# sensor_card.net
KiCad netlist of a schematic drawn in EAGLE
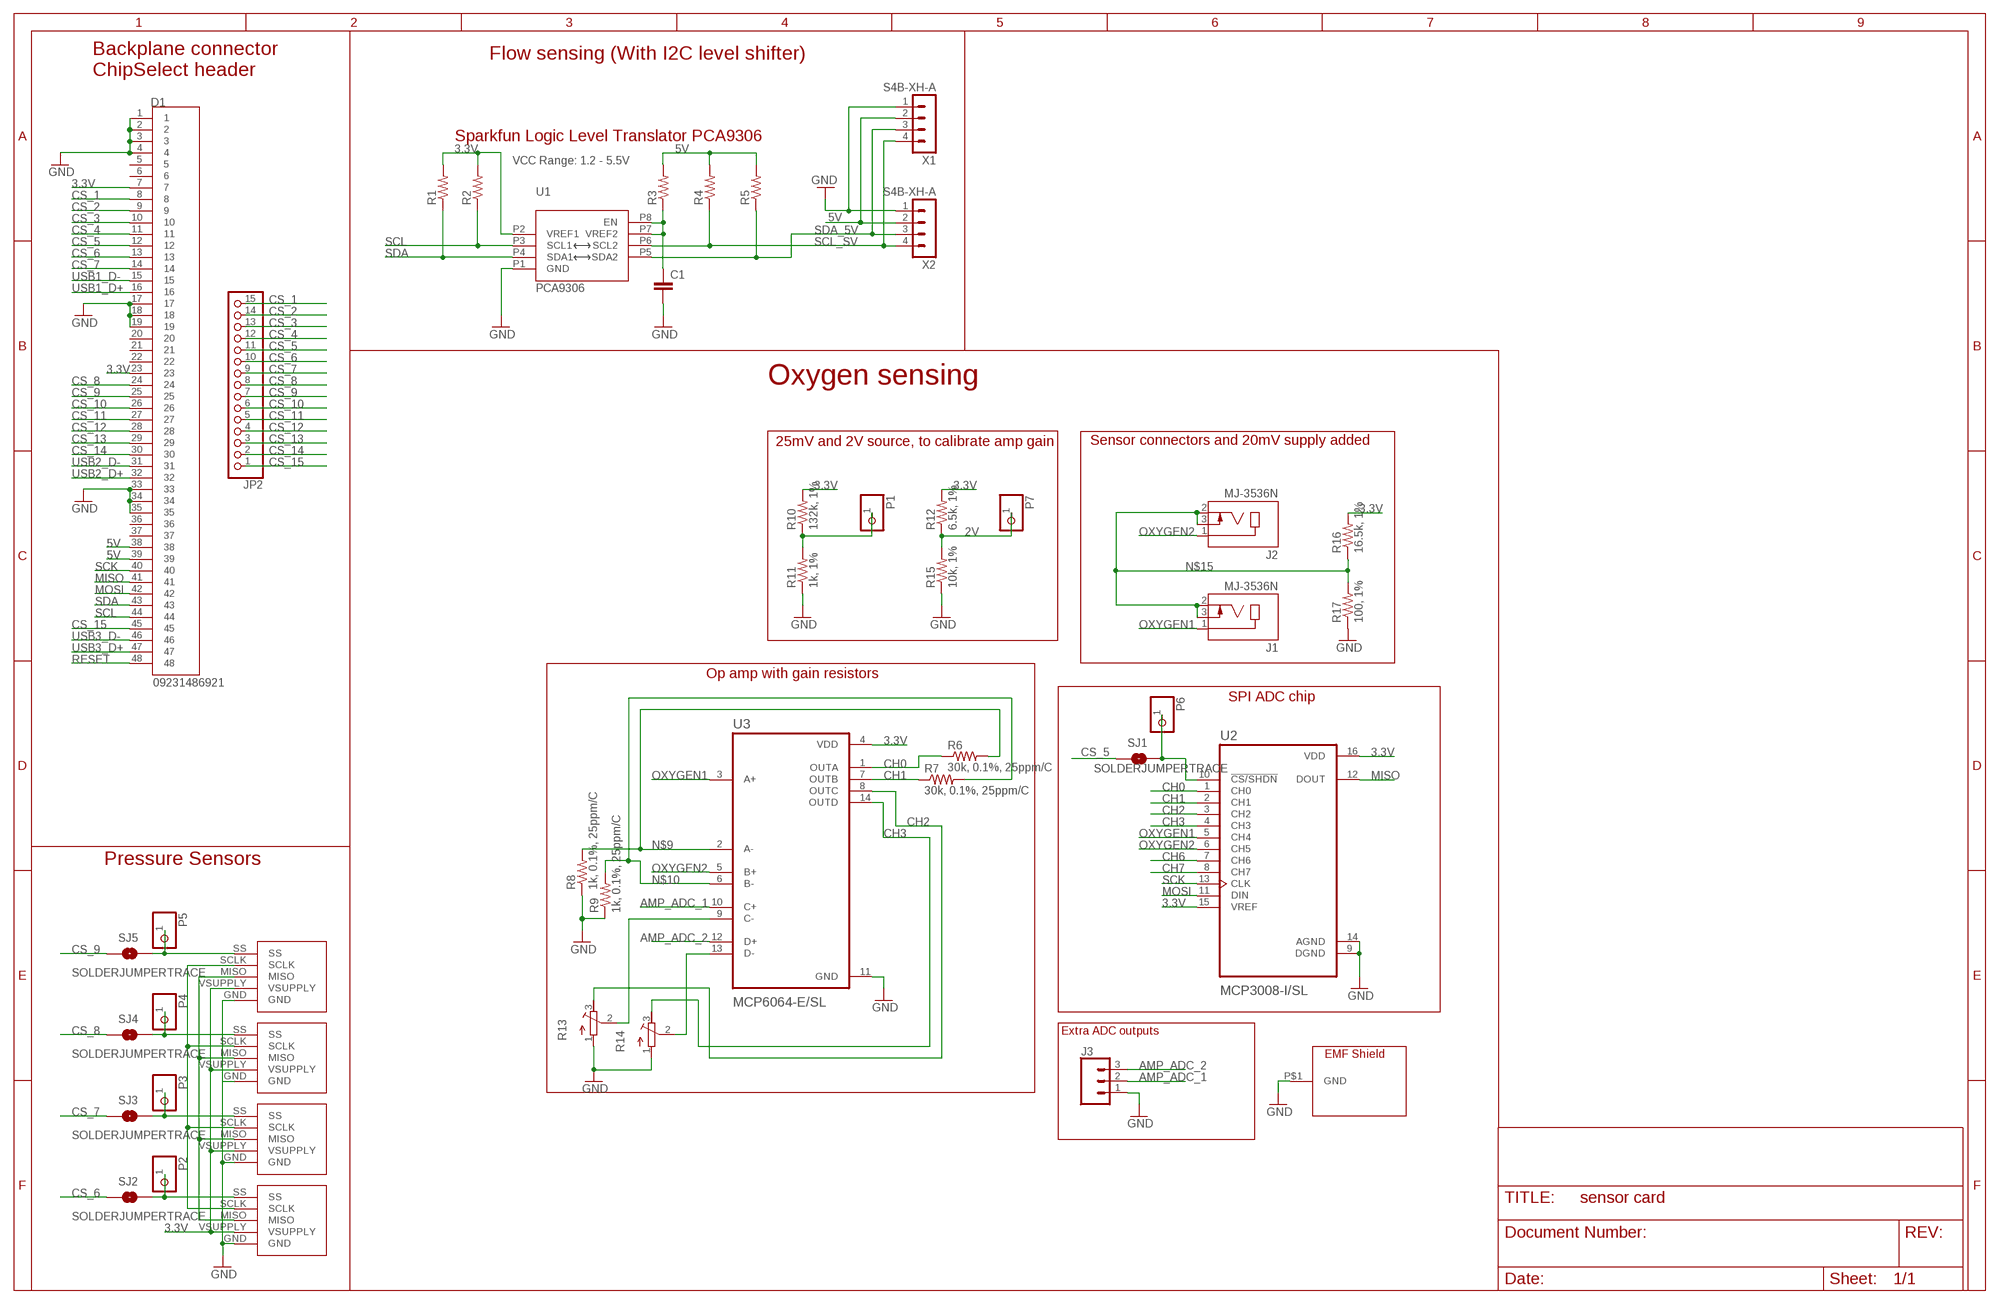
[diagram p0: schematic, sheet 1]

(export (version "E")
  (design (tool "Eeschema 10.0.6"))
  (components
    (comp (ref "C1")
      (value "100pF")
      (footprint "eagle-import:0805")
      (libsource (lib "eagle-import") (part "CAP0805"))
    )
    (comp (ref "D1")
      (value "09231486921")
      (footprint "eagle-import:HARTING_09231486921")
      (libsource (lib "eagle-import") (part "09231486921"))
    )
    (comp (ref "J1")
      (value "MJ-3536N")
      (footprint "eagle-import:CUI_MJ-3536N")
      (libsource (lib "eagle-import") (part "MJ-3536N"))
    )
    (comp (ref "J2")
      (value "MJ-3536N")
      (footprint "eagle-import:CUI_MJ-3536N")
      (libsource (lib "eagle-import") (part "MJ-3536N"))
    )
    (comp (ref "J3")
      (value "CONN_03")
      (footprint "eagle-import:1X03")
      (libsource (lib "eagle-import") (part "CONN_03"))
    )
    (comp (ref "JP2")
      (value "PINHD-1X15")
      (footprint "eagle-import:1X15")
      (libsource (lib "eagle-import") (part "PINHD-1X15"))
    )
    (comp (ref "P1")
      (value "PINHD-1X1")
      (footprint "eagle-import:1X01")
      (libsource (lib "eagle-import") (part "PINHD-1X1"))
    )
    (comp (ref "P2")
      (value "PINHD-1X1")
      (footprint "eagle-import:1X01")
      (libsource (lib "eagle-import") (part "PINHD-1X1"))
    )
    (comp (ref "P3")
      (value "PINHD-1X1")
      (footprint "eagle-import:1X01")
      (libsource (lib "eagle-import") (part "PINHD-1X1"))
    )
    (comp (ref "P4")
      (value "PINHD-1X1")
      (footprint "eagle-import:1X01")
      (libsource (lib "eagle-import") (part "PINHD-1X1"))
    )
    (comp (ref "P5")
      (value "PINHD-1X1")
      (footprint "eagle-import:1X01")
      (libsource (lib "eagle-import") (part "PINHD-1X1"))
    )
    (comp (ref "P6")
      (value "PINHD-1X1")
      (footprint "eagle-import:1X01")
      (libsource (lib "eagle-import") (part "PINHD-1X1"))
    )
    (comp (ref "P7")
      (value "PINHD-1X1")
      (footprint "eagle-import:1X01")
      (libsource (lib "eagle-import") (part "PINHD-1X1"))
    )
    (comp (ref "R1")
      (value "2.2k")
      (footprint "eagle-import:0805")
      (libsource (lib "eagle-import") (part "RESISTOR0805-RES"))
    )
    (comp (ref "R2")
      (value "2.2k")
      (footprint "eagle-import:0805")
      (libsource (lib "eagle-import") (part "RESISTOR0805-RES"))
    )
    (comp (ref "R3")
      (value "200K")
      (footprint "eagle-import:0805")
      (libsource (lib "eagle-import") (part "RESISTOR0805-RES"))
    )
    (comp (ref "R4")
      (value "2.2k")
      (footprint "eagle-import:0805")
      (libsource (lib "eagle-import") (part "RESISTOR0805-RES"))
    )
    (comp (ref "R5")
      (value "2.2k")
      (footprint "eagle-import:0805")
      (libsource (lib "eagle-import") (part "RESISTOR0805-RES"))
    )
    (comp (ref "R6")
      (value "30k, 0.1%, 25ppm/C")
      (footprint "eagle-import:0805")
      (libsource (lib "eagle-import") (part "RESISTOR0805-RES"))
    )
    (comp (ref "R7")
      (value "30k, 0.1%, 25ppm/C")
      (footprint "eagle-import:0805")
      (libsource (lib "eagle-import") (part "RESISTOR0805-RES"))
    )
    (comp (ref "R8")
      (value "1k, 0.1%, 25ppm/C")
      (footprint "eagle-import:0805")
      (libsource (lib "eagle-import") (part "RESISTOR0805-RES"))
    )
    (comp (ref "R9")
      (value "1k, 0.1%, 25ppm/C")
      (footprint "eagle-import:0805")
      (libsource (lib "eagle-import") (part "RESISTOR0805-RES"))
    )
    (comp (ref "R10")
      (value "132k, 1%")
      (footprint "eagle-import:0805")
      (libsource (lib "eagle-import") (part "RESISTOR0805-RES"))
    )
    (comp (ref "R11")
      (value "1k, 1%")
      (footprint "eagle-import:0805")
      (libsource (lib "eagle-import") (part "RESISTOR0805-RES"))
    )
    (comp (ref "R12")
      (value "6.5k, 1%")
      (footprint "eagle-import:0805")
      (libsource (lib "eagle-import") (part "RESISTOR0805-RES"))
    )
    (comp (ref "R13")
      (value "R-TRIMM3214W")
      (footprint "eagle-import:RTRIM3214W")
      (libsource (lib "eagle-import") (part "R-TRIMM3214W"))
    )
    (comp (ref "R14")
      (value "R-TRIMM3214W")
      (footprint "eagle-import:RTRIM3214W")
      (libsource (lib "eagle-import") (part "R-TRIMM3214W"))
    )
    (comp (ref "R15")
      (value "10k, 1%")
      (footprint "eagle-import:0805")
      (libsource (lib "eagle-import") (part "RESISTOR0805-RES"))
    )
    (comp (ref "R16")
      (value "16.5k, 1%")
      (footprint "eagle-import:0805")
      (libsource (lib "eagle-import") (part "RESISTOR0805-RES"))
    )
    (comp (ref "R17")
      (value "100, 1%")
      (footprint "eagle-import:0805")
      (libsource (lib "eagle-import") (part "RESISTOR0805-RES"))
    )
    (comp (ref "SJ1")
      (value "SOLDERJUMPERTRACE")
      (footprint "eagle-import:SJ_2S-TRACE")
      (libsource (lib "eagle-import") (part "SOLDERJUMPERTRACE"))
    )
    (comp (ref "SJ2")
      (value "SOLDERJUMPERTRACE")
      (footprint "eagle-import:SJ_2S-TRACE")
      (libsource (lib "eagle-import") (part "SOLDERJUMPERTRACE"))
    )
    (comp (ref "SJ3")
      (value "SOLDERJUMPERTRACE")
      (footprint "eagle-import:SJ_2S-TRACE")
      (libsource (lib "eagle-import") (part "SOLDERJUMPERTRACE"))
    )
    (comp (ref "SJ4")
      (value "SOLDERJUMPERTRACE")
      (footprint "eagle-import:SJ_2S-TRACE")
      (libsource (lib "eagle-import") (part "SOLDERJUMPERTRACE"))
    )
    (comp (ref "SJ5")
      (value "SOLDERJUMPERTRACE")
      (footprint "eagle-import:SJ_2S-TRACE")
      (libsource (lib "eagle-import") (part "SOLDERJUMPERTRACE"))
    )
    (comp (ref "U$1")
      (value "SCCDRRV100MDSA3SSCDRRV100MDSA3")
      (footprint "eagle-import:DIP1270W53P254L1303H508Q8B")
      (libsource (lib "eagle-import") (part "SCCDRRV100MDSA3SSCDRRV100MDSA3"))
    )
    (comp (ref "U$2")
      (value "EMI_SHIELD")
      (footprint "eagle-import:3671250")
      (libsource (lib "eagle-import") (part "EMI_SHIELD"))
    )
    (comp (ref "U$3")
      (value "SCCDRRV100MDSA3SSCDRRV100MDSA3")
      (footprint "eagle-import:DIP1270W53P254L1303H508Q8B")
      (libsource (lib "eagle-import") (part "SCCDRRV100MDSA3SSCDRRV100MDSA3"))
    )
    (comp (ref "U$4")
      (value "SCCDRRV100MDSA3SSCDRRV100MDSA3")
      (footprint "eagle-import:DIP1270W53P254L1303H508Q8B")
      (libsource (lib "eagle-import") (part "SCCDRRV100MDSA3SSCDRRV100MDSA3"))
    )
    (comp (ref "U$5")
      (value "SCCDRRV100MDSA3SSCDRRV100MDSA3")
      (footprint "eagle-import:DIP1270W53P254L1303H508Q8B")
      (libsource (lib "eagle-import") (part "SCCDRRV100MDSA3SSCDRRV100MDSA3"))
    )
    (comp (ref "U1")
      (value "PCA9306")
      (footprint "eagle-import:VSSOP_8PIN")
      (libsource (lib "eagle-import") (part "PCA9306VSSOP_8PIN"))
    )
    (comp (ref "U2")
      (value "MCP3008-I/SL")
      (footprint "eagle-import:SOIC127P600X175-16N")
      (libsource (lib "eagle-import") (part "MCP3008-I/SL"))
    )
    (comp (ref "U3")
      (value "MCP6064-E/SL")
      (footprint "eagle-import:SOIC127P600X175-14N")
      (libsource (lib "eagle-import") (part "MCP6064-E/SL"))
    )
    (comp (ref "X1")
      (value "S4B-XH-A")
      (footprint "eagle-import:S4B-XH-A")
      (libsource (lib "eagle-import") (part "S4B-XH-A"))
    )
    (comp (ref "X2")
      (value "S4B-XH-A")
      (footprint "eagle-import:S4B-XH-A")
      (libsource (lib "eagle-import") (part "S4B-XH-A"))
    )
  )
  (nets
    (net (code "1") (name "/2V") (class "Default")
      (node (ref "P7") (pin "1") (pinfunction "1_1") (pintype "passive"))
      (node (ref "R12") (pin "1") (pinfunction "1_1") (pintype "passive"))
      (node (ref "R15") (pin "2") (pinfunction "2_2") (pintype "passive"))
    )
    (net (code "2") (name "/3.3V") (class "Default")
      (node (ref "D1") (pin "23") (pinfunction "23_23") (pintype "passive"))
      (node (ref "D1") (pin "7") (pinfunction "7_7") (pintype "passive"))
      (node (ref "R1") (pin "2") (pinfunction "2_2") (pintype "passive"))
      (node (ref "R10") (pin "2") (pinfunction "2_2") (pintype "passive"))
      (node (ref "R12") (pin "2") (pinfunction "2_2") (pintype "passive"))
      (node (ref "R16") (pin "2") (pinfunction "2_2") (pintype "passive"))
      (node (ref "R2") (pin "2") (pinfunction "2_2") (pintype "passive"))
      (node (ref "U$1") (pin "VSUPPLY") (pinfunction "VSUPPLY_VSUPPLY") (pintype "bidirectional"))
      (node (ref "U$3") (pin "VSUPPLY") (pinfunction "VSUPPLY_VSUPPLY") (pintype "bidirectional"))
      (node (ref "U$4") (pin "VSUPPLY") (pinfunction "VSUPPLY_VSUPPLY") (pintype "bidirectional"))
      (node (ref "U$5") (pin "VSUPPLY") (pinfunction "VSUPPLY_VSUPPLY") (pintype "bidirectional"))
      (node (ref "U1") (pin "P2") (pinfunction "VREF1_P2") (pintype "power_in"))
      (node (ref "U2") (pin "15") (pinfunction "VREF_15") (pintype "input"))
      (node (ref "U2") (pin "16") (pinfunction "VDD_16") (pintype "power_in"))
      (node (ref "U3") (pin "4") (pinfunction "VDD_4") (pintype "power_in"))
    )
    (net (code "3") (name "/5V") (class "Default")
      (node (ref "D1") (pin "38") (pinfunction "38_38") (pintype "passive"))
      (node (ref "D1") (pin "39") (pinfunction "39_39") (pintype "passive"))
      (node (ref "R3") (pin "2") (pinfunction "2_2") (pintype "passive"))
      (node (ref "R4") (pin "2") (pinfunction "2_2") (pintype "passive"))
      (node (ref "R5") (pin "2") (pinfunction "2_2") (pintype "passive"))
      (node (ref "X1") (pin "2") (pinfunction "2_2") (pintype "passive"))
      (node (ref "X2") (pin "2") (pinfunction "2_2") (pintype "passive"))
    )
    (net (code "4") (name "/AMP_ADC_1") (class "Default")
      (node (ref "J3") (pin "2") (pinfunction "2_2") (pintype "passive"))
      (node (ref "U3") (pin "10") (pinfunction "C+_10") (pintype "bidirectional"))
    )
    (net (code "5") (name "/AMP_ADC_2") (class "Default")
      (node (ref "J3") (pin "3") (pinfunction "3_3") (pintype "passive"))
      (node (ref "U3") (pin "12") (pinfunction "D+_12") (pintype "bidirectional"))
    )
    (net (code "6") (name "/CH0") (class "Default")
      (node (ref "R6") (pin "1") (pinfunction "1_1") (pintype "passive"))
      (node (ref "U2") (pin "1") (pinfunction "CH0_1") (pintype "input"))
      (node (ref "U3") (pin "1") (pinfunction "OUTA_1") (pintype "output"))
    )
    (net (code "7") (name "/CH1") (class "Default")
      (node (ref "R7") (pin "1") (pinfunction "1_1") (pintype "passive"))
      (node (ref "U2") (pin "2") (pinfunction "CH1_2") (pintype "input"))
      (node (ref "U3") (pin "7") (pinfunction "OUTB_7") (pintype "output"))
    )
    (net (code "8") (name "/CH2") (class "Default")
      (node (ref "R13") (pin "3") (pinfunction "E_3") (pintype "passive"))
      (node (ref "U2") (pin "3") (pinfunction "CH2_3") (pintype "input"))
      (node (ref "U3") (pin "8") (pinfunction "OUTC_8") (pintype "output"))
    )
    (net (code "9") (name "/CH3") (class "Default")
      (node (ref "R14") (pin "3") (pinfunction "E_3") (pintype "passive"))
      (node (ref "U2") (pin "4") (pinfunction "CH3_4") (pintype "input"))
      (node (ref "U3") (pin "14") (pinfunction "OUTD_14") (pintype "output"))
    )
    (net (code "10") (name "/CH6") (class "Default")
      (node (ref "U2") (pin "7") (pinfunction "CH6_7") (pintype "input"))
    )
    (net (code "11") (name "/CH7") (class "Default")
      (node (ref "U2") (pin "8") (pinfunction "CH7_8") (pintype "input"))
    )
    (net (code "12") (name "/CS_1") (class "Default")
      (node (ref "D1") (pin "8") (pinfunction "8_8") (pintype "passive"))
      (node (ref "JP2") (pin "15") (pinfunction "15_15") (pintype "passive"))
    )
    (net (code "13") (name "/CS_2") (class "Default")
      (node (ref "D1") (pin "9") (pinfunction "9_9") (pintype "passive"))
      (node (ref "JP2") (pin "14") (pinfunction "14_14") (pintype "passive"))
    )
    (net (code "14") (name "/CS_3") (class "Default")
      (node (ref "D1") (pin "10") (pinfunction "10_10") (pintype "passive"))
      (node (ref "JP2") (pin "13") (pinfunction "13_13") (pintype "passive"))
    )
    (net (code "15") (name "/CS_4") (class "Default")
      (node (ref "D1") (pin "11") (pinfunction "11_11") (pintype "passive"))
      (node (ref "JP2") (pin "12") (pinfunction "12_12") (pintype "passive"))
    )
    (net (code "16") (name "/CS_5") (class "Default")
      (node (ref "D1") (pin "12") (pinfunction "12_12") (pintype "passive"))
      (node (ref "JP2") (pin "11") (pinfunction "11_11") (pintype "passive"))
      (node (ref "SJ1") (pin "1") (pinfunction "1_1") (pintype "passive"))
    )
    (net (code "17") (name "/CS_6") (class "Default")
      (node (ref "D1") (pin "13") (pinfunction "13_13") (pintype "passive"))
      (node (ref "JP2") (pin "10") (pinfunction "10_10") (pintype "passive"))
      (node (ref "SJ2") (pin "1") (pinfunction "1_1") (pintype "passive"))
    )
    (net (code "18") (name "/CS_7") (class "Default")
      (node (ref "D1") (pin "14") (pinfunction "14_14") (pintype "passive"))
      (node (ref "JP2") (pin "9") (pinfunction "9_9") (pintype "passive"))
      (node (ref "SJ3") (pin "1") (pinfunction "1_1") (pintype "passive"))
    )
    (net (code "19") (name "/CS_8") (class "Default")
      (node (ref "D1") (pin "24") (pinfunction "24_24") (pintype "passive"))
      (node (ref "JP2") (pin "8") (pinfunction "8_8") (pintype "passive"))
      (node (ref "SJ4") (pin "1") (pinfunction "1_1") (pintype "passive"))
    )
    (net (code "20") (name "/CS_9") (class "Default")
      (node (ref "D1") (pin "25") (pinfunction "25_25") (pintype "passive"))
      (node (ref "JP2") (pin "7") (pinfunction "7_7") (pintype "passive"))
      (node (ref "SJ5") (pin "1") (pinfunction "1_1") (pintype "passive"))
    )
    (net (code "21") (name "/CS_10") (class "Default")
      (node (ref "D1") (pin "26") (pinfunction "26_26") (pintype "passive"))
      (node (ref "JP2") (pin "6") (pinfunction "6_6") (pintype "passive"))
    )
    (net (code "22") (name "/CS_11") (class "Default")
      (node (ref "D1") (pin "27") (pinfunction "27_27") (pintype "passive"))
      (node (ref "JP2") (pin "5") (pinfunction "5_5") (pintype "passive"))
    )
    (net (code "23") (name "/CS_12") (class "Default")
      (node (ref "D1") (pin "28") (pinfunction "28_28") (pintype "passive"))
      (node (ref "JP2") (pin "4") (pinfunction "4_4") (pintype "passive"))
    )
    (net (code "24") (name "/CS_13") (class "Default")
      (node (ref "D1") (pin "29") (pinfunction "29_29") (pintype "passive"))
      (node (ref "JP2") (pin "3") (pinfunction "3_3") (pintype "passive"))
    )
    (net (code "25") (name "/CS_14") (class "Default")
      (node (ref "D1") (pin "30") (pinfunction "30_30") (pintype "passive"))
      (node (ref "JP2") (pin "2") (pinfunction "2_2") (pintype "passive"))
    )
    (net (code "26") (name "/CS_15") (class "Default")
      (node (ref "D1") (pin "45") (pinfunction "45_45") (pintype "passive"))
      (node (ref "JP2") (pin "1") (pinfunction "1_1") (pintype "passive"))
    )
    (net (code "27") (name "/MISO") (class "Default")
      (node (ref "D1") (pin "41") (pinfunction "41_41") (pintype "passive"))
      (node (ref "U$1") (pin "MISO") (pinfunction "MISO_MISO") (pintype "bidirectional"))
      (node (ref "U$3") (pin "MISO") (pinfunction "MISO_MISO") (pintype "bidirectional"))
      (node (ref "U$4") (pin "MISO") (pinfunction "MISO_MISO") (pintype "bidirectional"))
      (node (ref "U$5") (pin "MISO") (pinfunction "MISO_MISO") (pintype "bidirectional"))
      (node (ref "U2") (pin "12") (pinfunction "DOUT_12") (pintype "output"))
    )
    (net (code "28") (name "/MOSI") (class "Default")
      (node (ref "D1") (pin "42") (pinfunction "42_42") (pintype "passive"))
      (node (ref "U2") (pin "11") (pinfunction "DIN_11") (pintype "input"))
    )
    (net (code "29") (name "/N$9") (class "Default")
      (node (ref "R6") (pin "2") (pinfunction "2_2") (pintype "passive"))
      (node (ref "R8") (pin "2") (pinfunction "2_2") (pintype "passive"))
      (node (ref "U3") (pin "2") (pinfunction "A-_2") (pintype "bidirectional"))
    )
    (net (code "30") (name "/N$10") (class "Default")
      (node (ref "R7") (pin "2") (pinfunction "2_2") (pintype "passive"))
      (node (ref "R9") (pin "2") (pinfunction "2_2") (pintype "passive"))
      (node (ref "U3") (pin "6") (pinfunction "B-_6") (pintype "bidirectional"))
    )
    (net (code "31") (name "/N$15") (class "Default")
      (node (ref "J1") (pin "2") (pinfunction "2_2") (pintype "passive"))
      (node (ref "J1") (pin "3") (pinfunction "3_3") (pintype "passive"))
      (node (ref "J2") (pin "2") (pinfunction "2_2") (pintype "passive"))
      (node (ref "J2") (pin "3") (pinfunction "3_3") (pintype "passive"))
      (node (ref "R16") (pin "1") (pinfunction "1_1") (pintype "passive"))
      (node (ref "R17") (pin "2") (pinfunction "2_2") (pintype "passive"))
    )
    (net (code "32") (name "/OXYGEN1") (class "Default")
      (node (ref "J1") (pin "1") (pinfunction "1_1") (pintype "passive"))
      (node (ref "U2") (pin "5") (pinfunction "CH4_5") (pintype "input"))
      (node (ref "U3") (pin "3") (pinfunction "A+_3") (pintype "bidirectional"))
    )
    (net (code "33") (name "/OXYGEN2") (class "Default")
      (node (ref "J2") (pin "1") (pinfunction "1_1") (pintype "passive"))
      (node (ref "U2") (pin "6") (pinfunction "CH5_6") (pintype "input"))
      (node (ref "U3") (pin "5") (pinfunction "B+_5") (pintype "bidirectional"))
    )
    (net (code "34") (name "/RESET") (class "Default")
      (node (ref "D1") (pin "48") (pinfunction "48_48") (pintype "passive"))
    )
    (net (code "35") (name "/SCK") (class "Default")
      (node (ref "D1") (pin "40") (pinfunction "40_40") (pintype "passive"))
      (node (ref "U$1") (pin "SCLK") (pinfunction "SCLK_SCLK") (pintype "bidirectional"))
      (node (ref "U$3") (pin "SCLK") (pinfunction "SCLK_SCLK") (pintype "bidirectional"))
      (node (ref "U$4") (pin "SCLK") (pinfunction "SCLK_SCLK") (pintype "bidirectional"))
      (node (ref "U$5") (pin "SCLK") (pinfunction "SCLK_SCLK") (pintype "bidirectional"))
      (node (ref "U2") (pin "13") (pinfunction "CLK_13") (pintype "input"))
    )
    (net (code "36") (name "/SCL") (class "Default")
      (node (ref "D1") (pin "44") (pinfunction "44_44") (pintype "passive"))
      (node (ref "R2") (pin "1") (pinfunction "1_1") (pintype "passive"))
      (node (ref "U1") (pin "P3") (pinfunction "SCL1_P3") (pintype "bidirectional"))
    )
    (net (code "37") (name "/SCL_SV") (class "Default")
      (node (ref "R4") (pin "1") (pinfunction "1_1") (pintype "passive"))
      (node (ref "U1") (pin "P6") (pinfunction "SCL2_P6") (pintype "bidirectional"))
      (node (ref "X1") (pin "4") (pinfunction "4_4") (pintype "passive"))
      (node (ref "X2") (pin "4") (pinfunction "4_4") (pintype "passive"))
    )
    (net (code "38") (name "/SDA") (class "Default")
      (node (ref "D1") (pin "43") (pinfunction "43_43") (pintype "passive"))
      (node (ref "R1") (pin "1") (pinfunction "1_1") (pintype "passive"))
      (node (ref "U1") (pin "P4") (pinfunction "SDA1_P4") (pintype "bidirectional"))
    )
    (net (code "39") (name "/SDA_5V") (class "Default")
      (node (ref "R5") (pin "1") (pinfunction "1_1") (pintype "passive"))
      (node (ref "U1") (pin "P5") (pinfunction "SDA2_P5") (pintype "bidirectional"))
      (node (ref "X1") (pin "3") (pinfunction "3_3") (pintype "passive"))
      (node (ref "X2") (pin "3") (pinfunction "3_3") (pintype "passive"))
    )
    (net (code "40") (name "/USB1_D+") (class "Default")
      (node (ref "D1") (pin "16") (pinfunction "16_16") (pintype "passive"))
    )
    (net (code "41") (name "/USB1_D-") (class "Default")
      (node (ref "D1") (pin "15") (pinfunction "15_15") (pintype "passive"))
    )
    (net (code "42") (name "/USB2_D+") (class "Default")
      (node (ref "D1") (pin "32") (pinfunction "32_32") (pintype "passive"))
    )
    (net (code "43") (name "/USB2_D-") (class "Default")
      (node (ref "D1") (pin "31") (pinfunction "31_31") (pintype "passive"))
    )
    (net (code "44") (name "/USB3_D+") (class "Default")
      (node (ref "D1") (pin "47") (pinfunction "47_47") (pintype "passive"))
    )
    (net (code "45") (name "/USB3_D-") (class "Default")
      (node (ref "D1") (pin "46") (pinfunction "46_46") (pintype "passive"))
    )
    (net (code "46") (name "GND") (class "Default")
      (node (ref "C1") (pin "2") (pinfunction "2_2") (pintype "passive"))
      (node (ref "D1") (pin "1") (pinfunction "1_1") (pintype "passive"))
      (node (ref "D1") (pin "17") (pinfunction "17_17") (pintype "passive"))
      (node (ref "D1") (pin "18") (pinfunction "18_18") (pintype "passive"))
      (node (ref "D1") (pin "19") (pinfunction "19_19") (pintype "passive"))
      (node (ref "D1") (pin "2") (pinfunction "2_2") (pintype "passive"))
      (node (ref "D1") (pin "3") (pinfunction "3_3") (pintype "passive"))
      (node (ref "D1") (pin "33") (pinfunction "33_33") (pintype "passive"))
      (node (ref "D1") (pin "34") (pinfunction "34_34") (pintype "passive"))
      (node (ref "D1") (pin "35") (pinfunction "35_35") (pintype "passive"))
      (node (ref "D1") (pin "4") (pinfunction "4_4") (pintype "passive"))
      (node (ref "J3") (pin "1") (pinfunction "1_1") (pintype "passive"))
      (node (ref "R11") (pin "1") (pinfunction "1_1") (pintype "passive"))
      (node (ref "R13") (pin "1") (pinfunction "A_1") (pintype "passive"))
      (node (ref "R14") (pin "1") (pinfunction "A_1") (pintype "passive"))
      (node (ref "R15") (pin "1") (pinfunction "1_1") (pintype "passive"))
      (node (ref "R17") (pin "1") (pinfunction "1_1") (pintype "passive"))
      (node (ref "R8") (pin "1") (pinfunction "1_1") (pintype "passive"))
      (node (ref "R9") (pin "1") (pinfunction "1_1") (pintype "passive"))
      (node (ref "U$1") (pin "GND") (pinfunction "GND_GND") (pintype "bidirectional"))
      (node (ref "U$2") (pin "P$1") (pinfunction "GND_P$1") (pintype "bidirectional"))
      (node (ref "U$3") (pin "GND") (pinfunction "GND_GND") (pintype "bidirectional"))
      (node (ref "U$4") (pin "GND") (pinfunction "GND_GND") (pintype "bidirectional"))
      (node (ref "U$5") (pin "GND") (pinfunction "GND_GND") (pintype "bidirectional"))
      (node (ref "U1") (pin "P1") (pinfunction "GND_P1") (pintype "power_in"))
      (node (ref "U2") (pin "14") (pinfunction "AGND_14") (pintype "power_in"))
      (node (ref "U2") (pin "9") (pinfunction "DGND_9") (pintype "power_in"))
      (node (ref "U3") (pin "11") (pinfunction "GND_11") (pintype "power_in"))
      (node (ref "X1") (pin "1") (pinfunction "1_1") (pintype "passive"))
      (node (ref "X2") (pin "1") (pinfunction "1_1") (pintype "passive"))
    )
    (net (code "47") (name "Net-(P1-Pad1)") (class "Default")
      (node (ref "P1") (pin "1") (pinfunction "1_1") (pintype "passive"))
      (node (ref "R10") (pin "1") (pinfunction "1_1") (pintype "passive"))
      (node (ref "R11") (pin "2") (pinfunction "2_2") (pintype "passive"))
    )
    (net (code "48") (name "Net-(P2-Pad1)") (class "Default")
      (node (ref "P2") (pin "1") (pinfunction "1_1") (pintype "passive"))
      (node (ref "SJ2") (pin "2") (pinfunction "2_2") (pintype "passive"))
      (node (ref "U$5") (pin "SS") (pinfunction "SS_SS") (pintype "bidirectional"))
    )
    (net (code "49") (name "Net-(P3-Pad1)") (class "Default")
      (node (ref "P3") (pin "1") (pinfunction "1_1") (pintype "passive"))
      (node (ref "SJ3") (pin "2") (pinfunction "2_2") (pintype "passive"))
      (node (ref "U$4") (pin "SS") (pinfunction "SS_SS") (pintype "bidirectional"))
    )
    (net (code "50") (name "Net-(P4-Pad1)") (class "Default")
      (node (ref "P4") (pin "1") (pinfunction "1_1") (pintype "passive"))
      (node (ref "SJ4") (pin "2") (pinfunction "2_2") (pintype "passive"))
      (node (ref "U$3") (pin "SS") (pinfunction "SS_SS") (pintype "bidirectional"))
    )
    (net (code "51") (name "Net-(P5-Pad1)") (class "Default")
      (node (ref "P5") (pin "1") (pinfunction "1_1") (pintype "passive"))
      (node (ref "SJ5") (pin "2") (pinfunction "2_2") (pintype "passive"))
      (node (ref "U$1") (pin "SS") (pinfunction "SS_SS") (pintype "bidirectional"))
    )
    (net (code "52") (name "Net-(R13-S)") (class "Default")
      (node (ref "R13") (pin "2") (pinfunction "S_2") (pintype "passive"))
      (node (ref "U3") (pin "9") (pinfunction "C-_9") (pintype "bidirectional"))
    )
    (net (code "53") (name "Net-(R14-S)") (class "Default")
      (node (ref "R14") (pin "2") (pinfunction "S_2") (pintype "passive"))
      (node (ref "U3") (pin "13") (pinfunction "D-_13") (pintype "bidirectional"))
    )
    (net (code "54") (name "Net-(U1-EN)") (class "Default")
      (node (ref "C1") (pin "1") (pinfunction "1_1") (pintype "passive"))
      (node (ref "R3") (pin "1") (pinfunction "1_1") (pintype "passive"))
      (node (ref "U1") (pin "P7") (pinfunction "VREF2_P7") (pintype "power_in"))
      (node (ref "U1") (pin "P8") (pinfunction "EN_P8") (pintype "input"))
    )
    (net (code "55") (name "Net-(U2-~{CS{slash}SHDN})") (class "Default")
      (node (ref "P6") (pin "1") (pinfunction "1_1") (pintype "passive"))
      (node (ref "SJ1") (pin "2") (pinfunction "2_2") (pintype "passive"))
      (node (ref "U2") (pin "10") (pinfunction "~{CS/SHDN}_10") (pintype "input"))
    )
    (net (code "56") (name "unconnected-(D1-Pad5)") (class "Default")
      (node (ref "D1") (pin "5") (pinfunction "5_5") (pintype "passive"))
    )
    (net (code "57") (name "unconnected-(D1-Pad6)") (class "Default")
      (node (ref "D1") (pin "6") (pinfunction "6_6") (pintype "passive"))
    )
    (net (code "58") (name "unconnected-(D1-Pad20)") (class "Default")
      (node (ref "D1") (pin "20") (pinfunction "20_20") (pintype "passive"))
    )
    (net (code "59") (name "unconnected-(D1-Pad21)") (class "Default")
      (node (ref "D1") (pin "21") (pinfunction "21_21") (pintype "passive"))
    )
    (net (code "60") (name "unconnected-(D1-Pad22)") (class "Default")
      (node (ref "D1") (pin "22") (pinfunction "22_22") (pintype "passive"))
    )
    (net (code "61") (name "unconnected-(D1-Pad36)") (class "Default")
      (node (ref "D1") (pin "36") (pinfunction "36_36") (pintype "passive"))
    )
    (net (code "62") (name "unconnected-(D1-Pad37)") (class "Default")
      (node (ref "D1") (pin "37") (pinfunction "37_37") (pintype "passive"))
    )
  )
)
